# Sheet_1_2022-09-27.net
KiCad netlist of a schematic drawn in Altium Designer
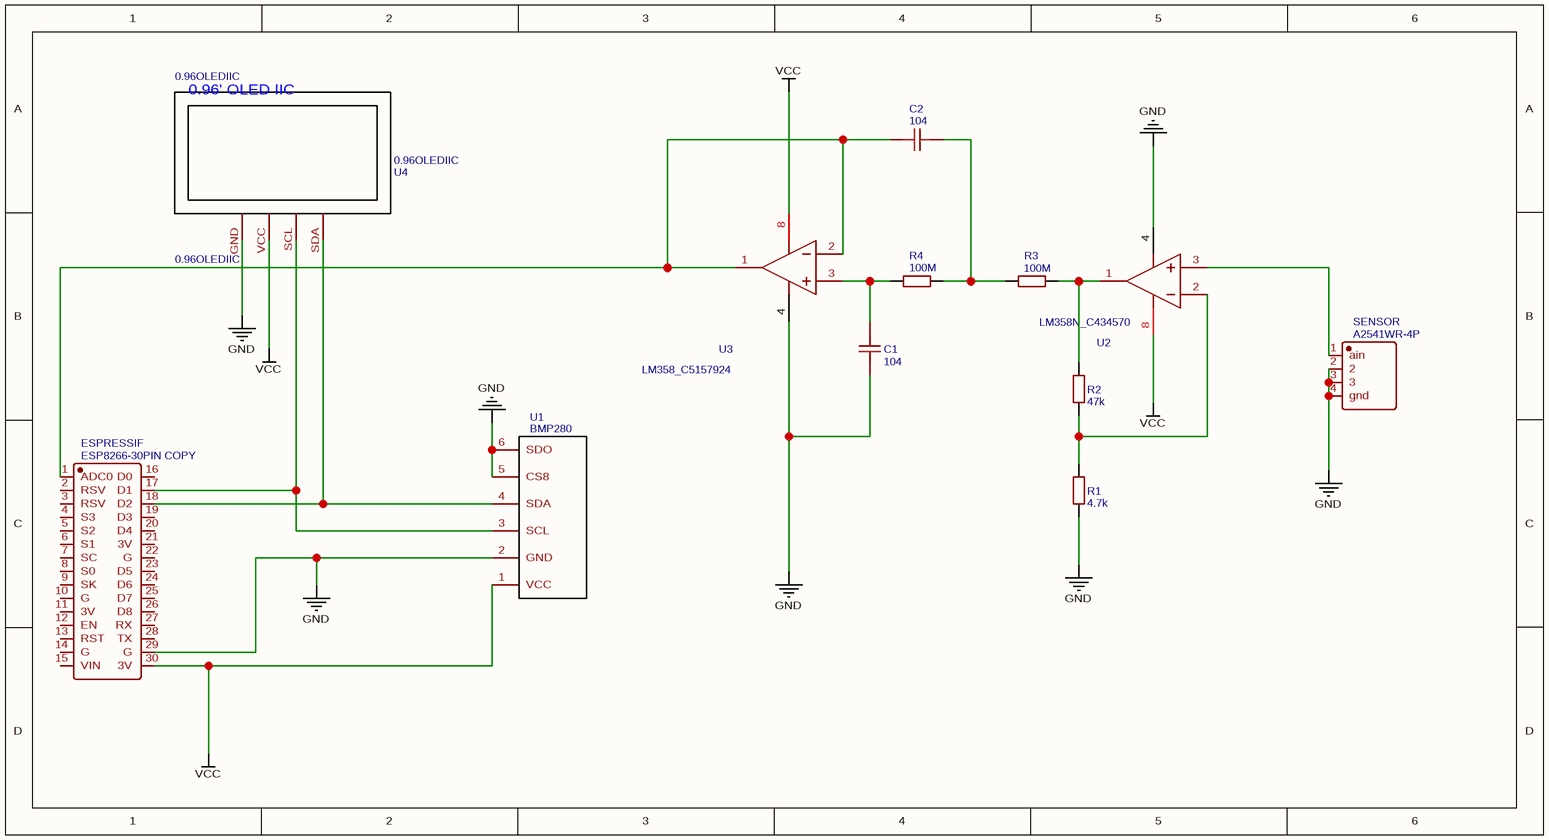
[diagram p0: Sheet_1_2022-09-27.schdoc]

(export (version "E")
  (design (tool "Eeschema 10.0.6"))
  (components
    (comp (ref "C1")
      (value "104")
      (fields
        (field (name "BOM_SUPPLIER PART") "C1622251")
        (field (name "BOM_MANUFACTURER PART") "RCER71E475K2DBH03A")
        (field (name "CONTRIBUTOR") "LCSC")
      )
      (libsource (lib "altium-import") (part "root_1_104_"))
    )
    (comp (ref "C2")
      (value "104")
      (fields
        (field (name "BOM_SUPPLIER PART") "C1622251")
        (field (name "BOM_MANUFACTURER PART") "RCER71E475K2DBH03A")
        (field (name "CONTRIBUTOR") "LCSC")
      )
      (libsource (lib "altium-import") (part "root_0_104_"))
    )
    (comp (ref "ESPRESSIF")
      (value "ESP8266-30PIN COPY")
      (fields (field (name "CONTRIBUTOR") "123r3"))
      (libsource (lib "altium-import") (part "root_0_ESP8266-30PIN COPY_"))
    )
    (comp (ref "R1")
      (value "4.7k")
      (fields
        (field (name "BOM_MANUFACTURER PART") "MGR02SJ0302AA0")
        (field (name "BOM_SUPPLIER PART") "C74658")
      )
      (libsource (lib "altium-import") (part "root_1_4.7k_"))
    )
    (comp (ref "R2")
      (value "47k")
      (fields
        (field (name "BOM_MANUFACTURER PART") "MGR02SJ0302AA0")
        (field (name "BOM_SUPPLIER PART") "C74658")
      )
      (libsource (lib "altium-import") (part "root_1_47k_"))
    )
    (comp (ref "R3")
      (value "100M")
      (fields
        (field (name "BOM_MANUFACTURER PART") "MGR02SJ0302AA0")
        (field (name "BOM_SUPPLIER PART") "C74658")
      )
      (libsource (lib "altium-import") (part "root_0_100M_"))
    )
    (comp (ref "R4")
      (value "100M")
      (fields
        (field (name "BOM_MANUFACTURER PART") "MGR02SJ0302AA0")
        (field (name "BOM_SUPPLIER PART") "C74658")
      )
      (libsource (lib "altium-import") (part "root_0_100M_"))
    )
    (comp (ref "SENSOR")
      (value "A2541WR-4P")
      (fields (field (name "BOM_SUPPLIER PART") "C225490") (field (name "CONTRIBUTOR") "LCSC"))
      (libsource (lib "altium-import") (part "root_0_A2541WR-4P_"))
    )
    (comp (ref "U1")
      (value "BMP280")
      (fields (field (name "CONTRIBUTOR") "eggfly"))
      (libsource (lib "altium-import") (part "root_2_BMP280_"))
    )
    (comp (ref "U2")
      (value "LM358N_C434570")
      (fields
        (field (name "BOM_SUPPLIER PART") "C434570")
        (field (name "BOM_MANUFACTURER PART") "LM358N")
        (field (name "SUBPART_NO") "1")
        (field (name "CONTRIBUTOR") "LCSC")
      )
      (libsource (lib "altium-import") (part "root_0_LM358N_C434570_"))
    )
    (comp (ref "U3")
      (value "LM358_C5157924")
      (fields
        (field (name "BOM_SUPPLIER PART") "C5157924")
        (field (name "BOM_MANUFACTURER PART") "LM358")
        (field (name "SUBPART_NO") "1")
        (field (name "CONTRIBUTOR") "lcsc")
      )
      (libsource (lib "altium-import") (part "root_0_LM358_C5157924_"))
    )
    (comp (ref "U4")
      (value "0.96OLEDIIC")
      (fields (field (name "CONTRIBUTOR") "fyf132465798"))
      (libsource (lib "altium-import") (part "root_0_0.96OLEDIIC_"))
    )
  )
  (nets
    (net (code "1") (name "GND") (class "Default")
      (node (ref "C1") (pin "1") (pinfunction "1_1") (pintype "passive"))
      (node (ref "ESPRESSIF") (pin "29") (pinfunction "G_29") (pintype "passive"))
      (node (ref "R1") (pin "1") (pinfunction "1_1") (pintype "passive"))
      (node (ref "SENSOR") (pin "2") (pinfunction "2_2") (pintype "passive"))
      (node (ref "SENSOR") (pin "3") (pinfunction "3_3") (pintype "passive"))
      (node (ref "SENSOR") (pin "4") (pinfunction "gnd_4") (pintype "passive"))
      (node (ref "U1") (pin "2") (pinfunction "GND_2") (pintype "passive"))
      (node (ref "U1") (pin "5") (pinfunction "CS8_5") (pintype "passive"))
      (node (ref "U1") (pin "6") (pinfunction "SDO_6") (pintype "passive"))
      (node (ref "U2") (pin "4") (pinfunction "GND_4") (pintype "passive"))
      (node (ref "U3") (pin "4") (pinfunction "GND_4") (pintype "passive"))
      (node (ref "U4") (pin "GND") (pinfunction "GND_GND") (pintype "passive"))
    )
    (net (code "2") (name "Net-(C2-Pad2)") (class "Default")
      (node (ref "C2") (pin "2") (pinfunction "2_2") (pintype "passive"))
      (node (ref "R3") (pin "1") (pinfunction "1_1") (pintype "passive"))
      (node (ref "R4") (pin "2") (pinfunction "2_2") (pintype "passive"))
    )
    (net (code "3") (name "Net-(ESPRESSIF-ADC0)") (class "Default")
      (node (ref "C2") (pin "1") (pinfunction "1_1") (pintype "passive"))
      (node (ref "ESPRESSIF") (pin "1") (pinfunction "ADC0_1") (pintype "passive"))
      (node (ref "U3") (pin "1") (pinfunction "OUT1_1") (pintype "passive"))
      (node (ref "U3") (pin "2") (pinfunction "IN1-_2") (pintype "passive"))
    )
    (net (code "4") (name "Net-(ESPRESSIF-D1)") (class "Default")
      (node (ref "ESPRESSIF") (pin "17") (pinfunction "D1_17") (pintype "passive"))
      (node (ref "U1") (pin "3") (pinfunction "SCL_3") (pintype "passive"))
      (node (ref "U4") (pin "SCL") (pinfunction "SCL_SCL") (pintype "passive"))
    )
    (net (code "5") (name "Net-(ESPRESSIF-D2)") (class "Default")
      (node (ref "ESPRESSIF") (pin "18") (pinfunction "D2_18") (pintype "passive"))
      (node (ref "U1") (pin "4") (pinfunction "SDA_4") (pintype "passive"))
      (node (ref "U4") (pin "SDA") (pinfunction "SDA_SDA") (pintype "passive"))
    )
    (net (code "6") (name "Net-(SENSOR-ain)") (class "Default")
      (node (ref "SENSOR") (pin "1") (pinfunction "ain_1") (pintype "passive"))
      (node (ref "U2") (pin "3") (pinfunction "IN1+_3") (pintype "passive"))
    )
    (net (code "7") (name "Net-(U2-IN1-)") (class "Default")
      (node (ref "R1") (pin "2") (pinfunction "2_2") (pintype "passive"))
      (node (ref "R2") (pin "1") (pinfunction "1_1") (pintype "passive"))
      (node (ref "U2") (pin "2") (pinfunction "IN1-_2") (pintype "passive"))
    )
    (net (code "8") (name "Net-(U2-OUT1)") (class "Default")
      (node (ref "R2") (pin "2") (pinfunction "2_2") (pintype "passive"))
      (node (ref "R3") (pin "2") (pinfunction "2_2") (pintype "passive"))
      (node (ref "U2") (pin "1") (pinfunction "OUT1_1") (pintype "passive"))
    )
    (net (code "9") (name "Net-(U3-IN1+)") (class "Default")
      (node (ref "C1") (pin "2") (pinfunction "2_2") (pintype "passive"))
      (node (ref "R4") (pin "1") (pinfunction "1_1") (pintype "passive"))
      (node (ref "U3") (pin "3") (pinfunction "IN1+_3") (pintype "passive"))
    )
    (net (code "10") (name "VCC") (class "Default")
      (node (ref "ESPRESSIF") (pin "30") (pinfunction "3V_30") (pintype "passive"))
      (node (ref "U1") (pin "1") (pinfunction "VCC_1") (pintype "passive"))
      (node (ref "U2") (pin "8") (pinfunction "VCC_8") (pintype "passive"))
      (node (ref "U3") (pin "8") (pinfunction "VCC_8") (pintype "passive"))
      (node (ref "U4") (pin "VCC") (pinfunction "VCC_VCC") (pintype "passive"))
    )
    (net (code "11") (name "unconnected-(ESPRESSIF-3V-Pad11)") (class "Default")
      (node (ref "ESPRESSIF") (pin "11") (pinfunction "3V_11") (pintype "passive"))
    )
    (net (code "12") (name "unconnected-(ESPRESSIF-3V-Pad21)") (class "Default")
      (node (ref "ESPRESSIF") (pin "21") (pinfunction "3V_21") (pintype "passive"))
    )
    (net (code "13") (name "unconnected-(ESPRESSIF-D0-Pad16)") (class "Default")
      (node (ref "ESPRESSIF") (pin "16") (pinfunction "D0_16") (pintype "passive"))
    )
    (net (code "14") (name "unconnected-(ESPRESSIF-D3-Pad19)") (class "Default")
      (node (ref "ESPRESSIF") (pin "19") (pinfunction "D3_19") (pintype "passive"))
    )
    (net (code "15") (name "unconnected-(ESPRESSIF-D4-Pad20)") (class "Default")
      (node (ref "ESPRESSIF") (pin "20") (pinfunction "D4_20") (pintype "passive"))
    )
    (net (code "16") (name "unconnected-(ESPRESSIF-D5-Pad23)") (class "Default")
      (node (ref "ESPRESSIF") (pin "23") (pinfunction "D5_23") (pintype "passive"))
    )
    (net (code "17") (name "unconnected-(ESPRESSIF-D6-Pad24)") (class "Default")
      (node (ref "ESPRESSIF") (pin "24") (pinfunction "D6_24") (pintype "passive"))
    )
    (net (code "18") (name "unconnected-(ESPRESSIF-D7-Pad25)") (class "Default")
      (node (ref "ESPRESSIF") (pin "25") (pinfunction "D7_25") (pintype "passive"))
    )
    (net (code "19") (name "unconnected-(ESPRESSIF-D8-Pad26)") (class "Default")
      (node (ref "ESPRESSIF") (pin "26") (pinfunction "D8_26") (pintype "passive"))
    )
    (net (code "20") (name "unconnected-(ESPRESSIF-EN-Pad12)") (class "Default")
      (node (ref "ESPRESSIF") (pin "12") (pinfunction "EN_12") (pintype "passive"))
    )
    (net (code "21") (name "unconnected-(ESPRESSIF-G-Pad10)") (class "Default")
      (node (ref "ESPRESSIF") (pin "10") (pinfunction "G_10") (pintype "passive"))
    )
    (net (code "22") (name "unconnected-(ESPRESSIF-G-Pad14)") (class "Default")
      (node (ref "ESPRESSIF") (pin "14") (pinfunction "G_14") (pintype "passive"))
    )
    (net (code "23") (name "unconnected-(ESPRESSIF-G-Pad22)") (class "Default")
      (node (ref "ESPRESSIF") (pin "22") (pinfunction "G_22") (pintype "passive"))
    )
    (net (code "24") (name "unconnected-(ESPRESSIF-RST-Pad13)") (class "Default")
      (node (ref "ESPRESSIF") (pin "13") (pinfunction "RST_13") (pintype "passive"))
    )
    (net (code "25") (name "unconnected-(ESPRESSIF-RSV-Pad2)") (class "Default")
      (node (ref "ESPRESSIF") (pin "2") (pinfunction "RSV_2") (pintype "passive"))
    )
    (net (code "26") (name "unconnected-(ESPRESSIF-RSV-Pad3)") (class "Default")
      (node (ref "ESPRESSIF") (pin "3") (pinfunction "RSV_3") (pintype "passive"))
    )
    (net (code "27") (name "unconnected-(ESPRESSIF-RX-Pad27)") (class "Default")
      (node (ref "ESPRESSIF") (pin "27") (pinfunction "RX_27") (pintype "passive"))
    )
    (net (code "28") (name "unconnected-(ESPRESSIF-S0-Pad8)") (class "Default")
      (node (ref "ESPRESSIF") (pin "8") (pinfunction "S0_8") (pintype "passive"))
    )
    (net (code "29") (name "unconnected-(ESPRESSIF-S1-Pad6)") (class "Default")
      (node (ref "ESPRESSIF") (pin "6") (pinfunction "S1_6") (pintype "passive"))
    )
    (net (code "30") (name "unconnected-(ESPRESSIF-S2-Pad5)") (class "Default")
      (node (ref "ESPRESSIF") (pin "5") (pinfunction "S2_5") (pintype "passive"))
    )
    (net (code "31") (name "unconnected-(ESPRESSIF-S3-Pad4)") (class "Default")
      (node (ref "ESPRESSIF") (pin "4") (pinfunction "S3_4") (pintype "passive"))
    )
    (net (code "32") (name "unconnected-(ESPRESSIF-SC-Pad7)") (class "Default")
      (node (ref "ESPRESSIF") (pin "7") (pinfunction "SC_7") (pintype "passive"))
    )
    (net (code "33") (name "unconnected-(ESPRESSIF-SK-Pad9)") (class "Default")
      (node (ref "ESPRESSIF") (pin "9") (pinfunction "SK_9") (pintype "passive"))
    )
    (net (code "34") (name "unconnected-(ESPRESSIF-TX-Pad28)") (class "Default")
      (node (ref "ESPRESSIF") (pin "28") (pinfunction "TX_28") (pintype "passive"))
    )
    (net (code "35") (name "unconnected-(ESPRESSIF-VIN-Pad15)") (class "Default")
      (node (ref "ESPRESSIF") (pin "15") (pinfunction "VIN_15") (pintype "passive"))
    )
  )
)
